# LoRa_GPS_Track_v1_2.net
KiCad netlist of a schematic drawn in EAGLE
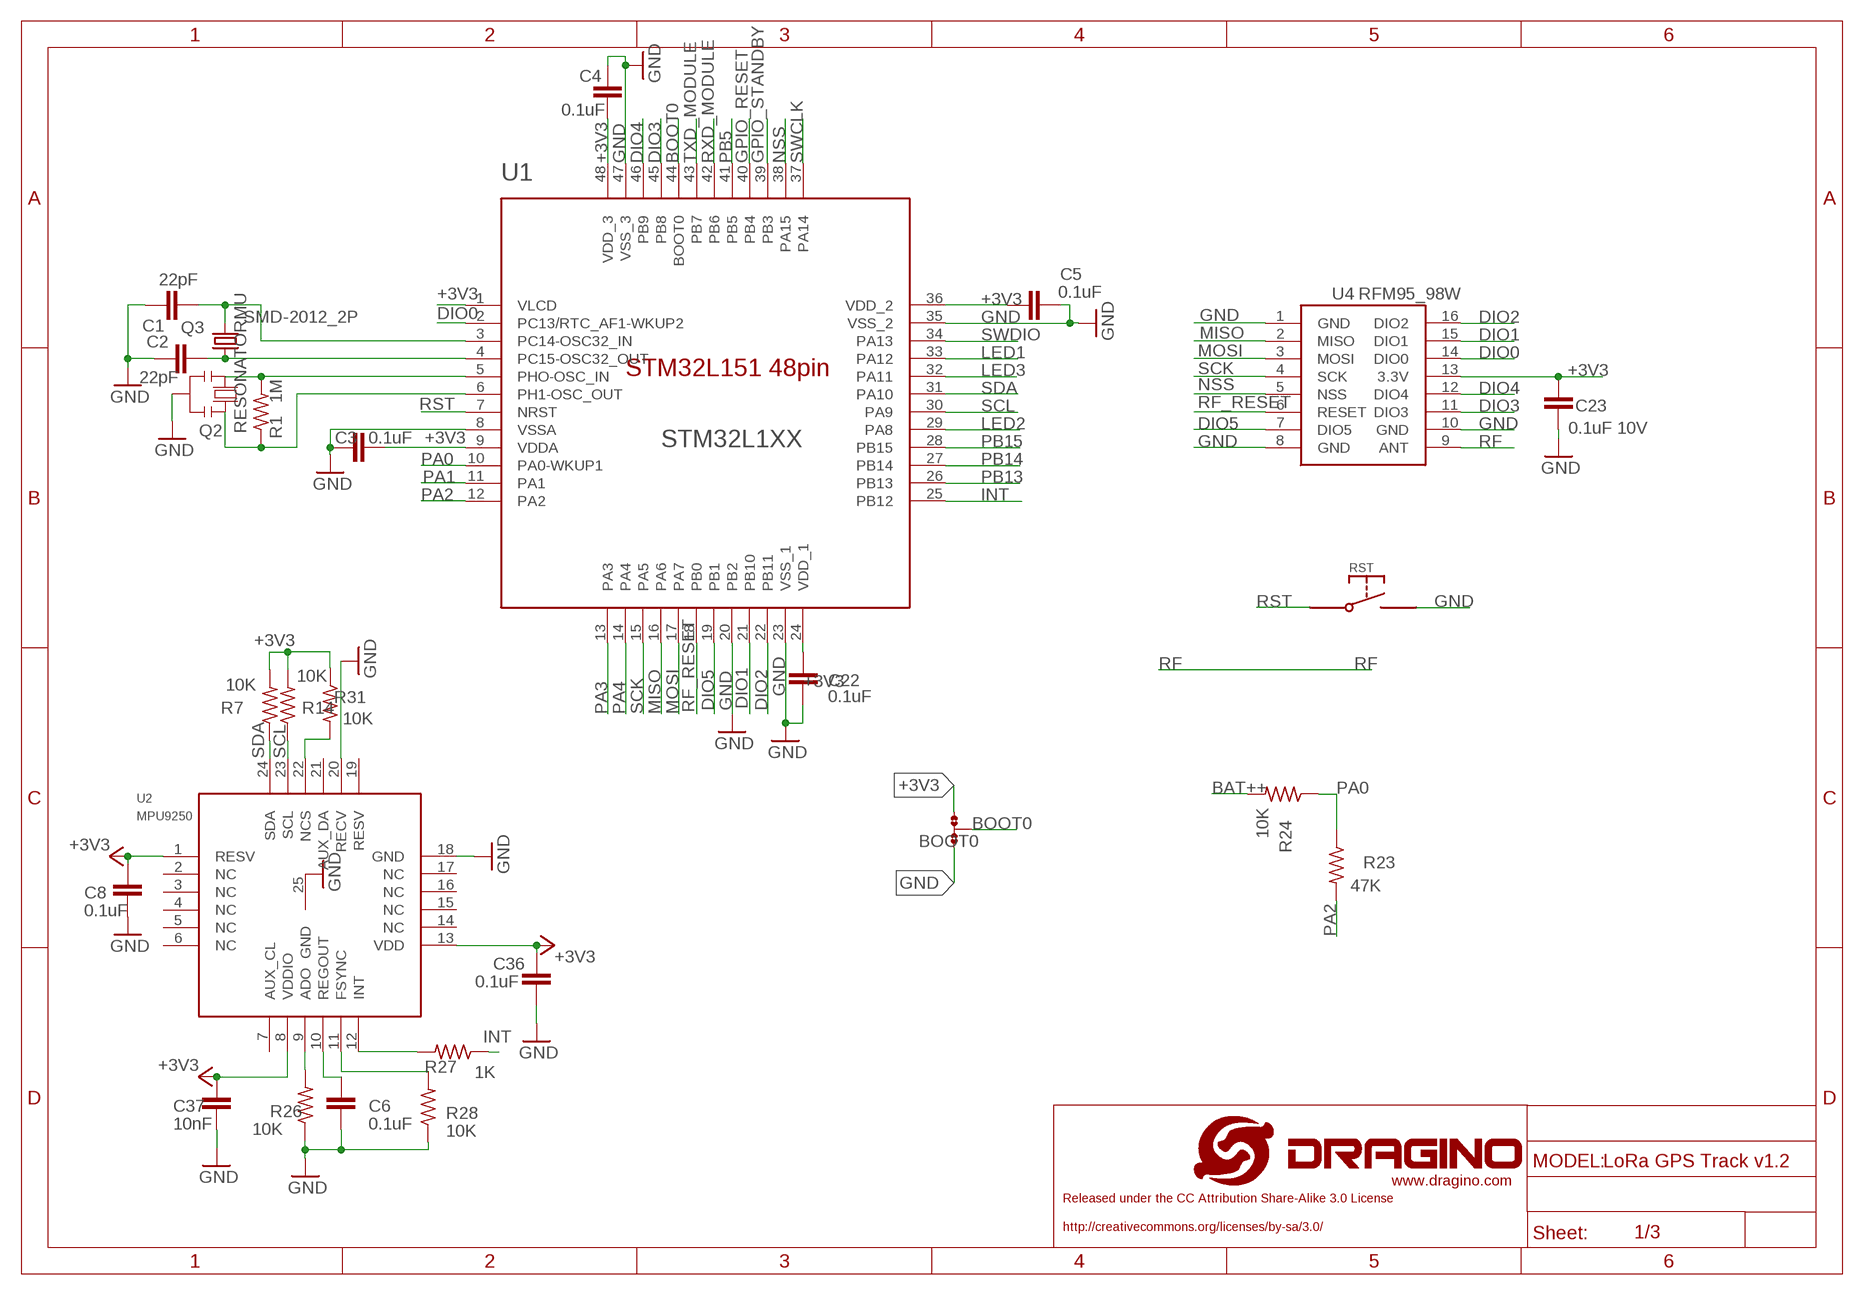
[diagram p0: schematic, sheet 1]
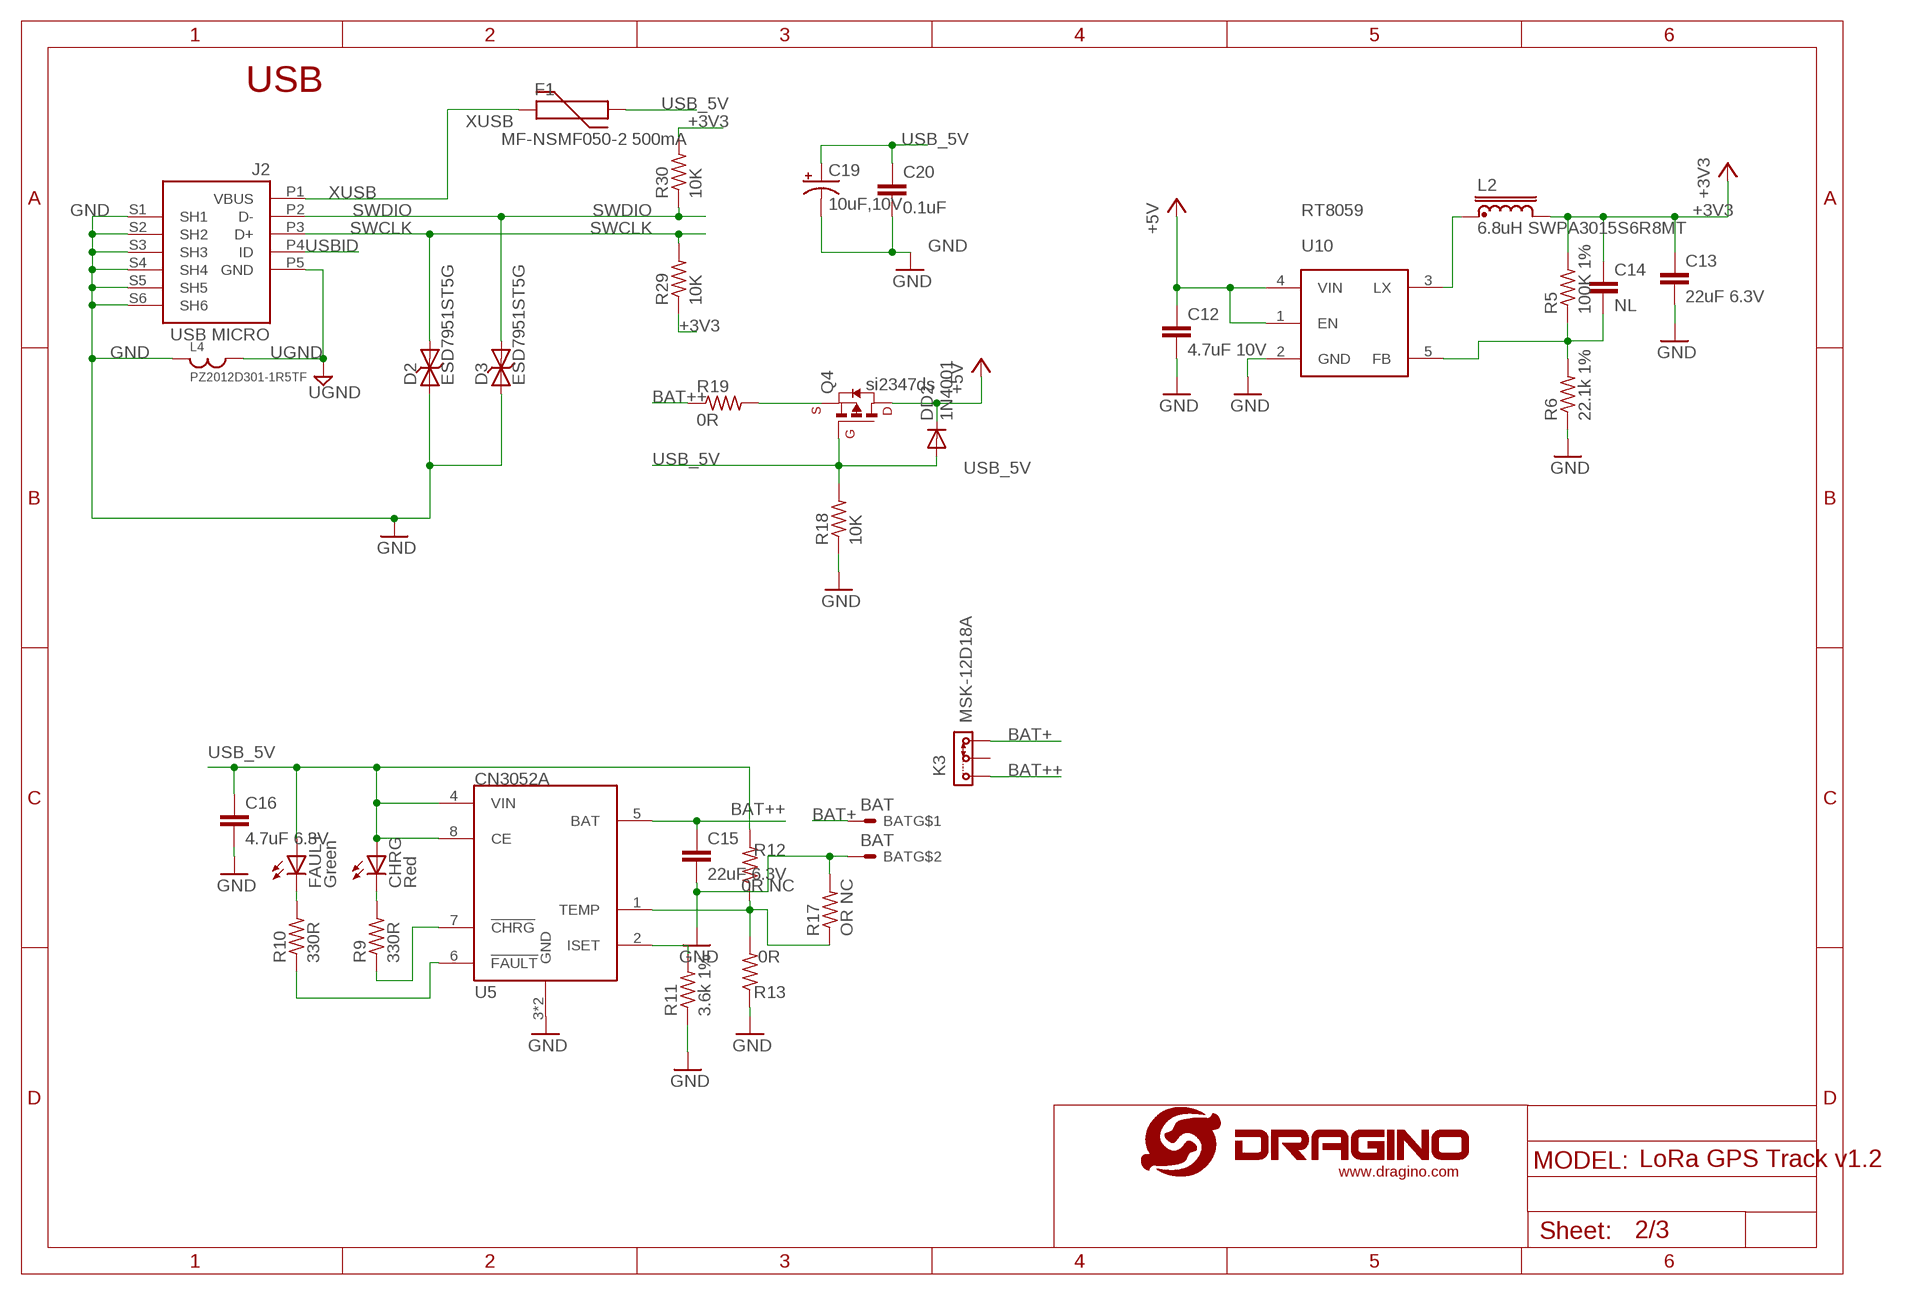
[diagram p1: schematic, sheet 2]
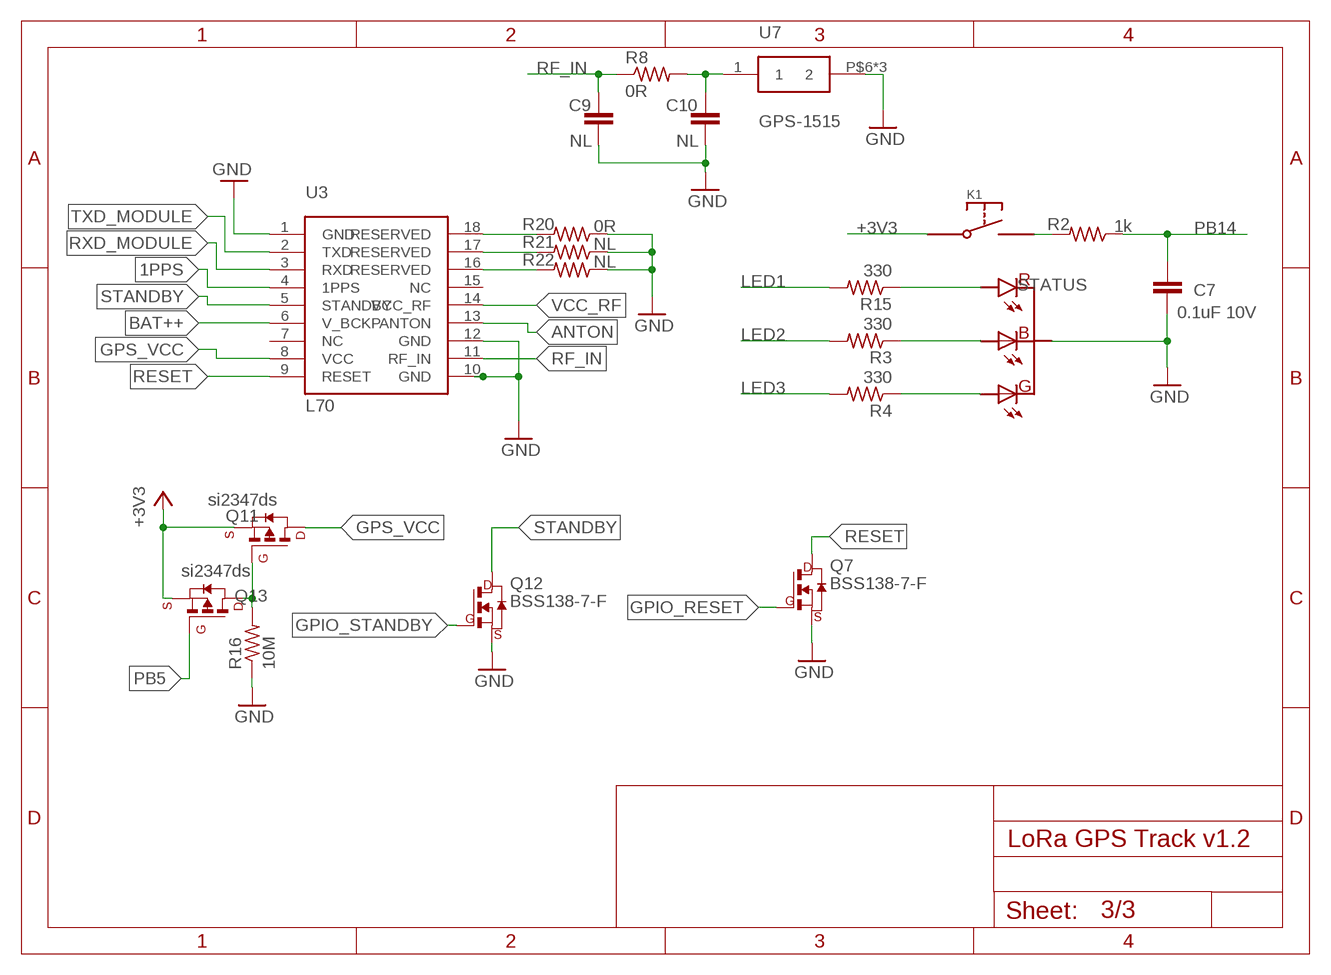
[diagram p2: schematic, sheet 3]

(export (version "E")
  (design (tool "Eeschema 10.0.6"))
  (components
    (comp (ref "C7")
      (value "0.1uF 10V")
      (footprint "eagle-import:C0402")
      (libsource (lib "eagle-import") (part "dragino-passive_C-EUC0402"))
    )
    (comp (ref "C9")
      (value "NL")
      (footprint "eagle-import:C0402")
      (libsource (lib "eagle-import") (part "dragino-passive_C-EUC0402"))
    )
    (comp (ref "C10")
      (value "NL")
      (footprint "eagle-import:C0402")
      (libsource (lib "eagle-import") (part "dragino-passive_C-EUC0402"))
    )
    (comp (ref "K1")
      (value "S-LAY")
      (footprint "eagle-import:KEY")
      (libsource (lib "eagle-import") (part "S-LAY"))
    )
    (comp (ref "Q7")
      (value "BSS138-7-F")
      (footprint "eagle-import:SOT-23")
      (libsource (lib "eagle-import") (part "NMOSFET"))
    )
    (comp (ref "Q11")
      (value "si2347ds")
      (footprint "eagle-import:SOT-23-HIGH-POWER")
      (libsource (lib "eagle-import") (part "P-MOSFET_HP"))
    )
    (comp (ref "Q12")
      (value "BSS138-7-F")
      (footprint "eagle-import:SOT-23")
      (libsource (lib "eagle-import") (part "NMOSFET"))
    )
    (comp (ref "Q13")
      (value "si2347ds")
      (footprint "eagle-import:SOT-23-HIGH-POWER")
      (libsource (lib "eagle-import") (part "P-MOSFET_HP"))
    )
    (comp (ref "R2")
      (value "1k")
      (footprint "eagle-import:R0402")
      (libsource (lib "eagle-import") (part "R-US_R0402"))
    )
    (comp (ref "R3")
      (value "330")
      (footprint "eagle-import:R0402")
      (libsource (lib "eagle-import") (part "R-US_R0402"))
    )
    (comp (ref "R4")
      (value "330")
      (footprint "eagle-import:R0402")
      (libsource (lib "eagle-import") (part "R-US_R0402"))
    )
    (comp (ref "R8")
      (value "0R")
      (footprint "eagle-import:R0402")
      (libsource (lib "eagle-import") (part "R-US_R0402"))
    )
    (comp (ref "R15")
      (value "330")
      (footprint "eagle-import:R0402")
      (libsource (lib "eagle-import") (part "R-US_R0402"))
    )
    (comp (ref "R16")
      (value "10M")
      (footprint "eagle-import:R0402")
      (libsource (lib "eagle-import") (part "R-US_R0402"))
    )
    (comp (ref "R20")
      (value "0R")
      (footprint "eagle-import:R0402")
      (libsource (lib "eagle-import") (part "R-US_R0402"))
    )
    (comp (ref "R21")
      (value "NL")
      (footprint "eagle-import:R0402")
      (libsource (lib "eagle-import") (part "R-US_R0402"))
    )
    (comp (ref "R22")
      (value "NL")
      (footprint "eagle-import:R0402")
      (libsource (lib "eagle-import") (part "R-US_R0402"))
    )
    (comp (ref "STATUS")
      (value "LED-RGB-THR-5MM-GNDSMD-3528")
      (footprint "eagle-import:LED-3528")
      (libsource (lib "eagle-import") (part "LED-RGB-THR-5MM-GNDSMD-3528"))
    )
    (comp (ref "U3")
      (value "L70")
      (footprint "eagle-import:L70")
      (libsource (lib "eagle-import") (part "L70"))
    )
    (comp (ref "U7")
      (value "GPS-1515")
      (footprint "eagle-import:GPS-15_15")
      (libsource (lib "eagle-import") (part "GPS-1515"))
    )
    (comp (ref "BAT")
      (value "BAT")
      (footprint "eagle-import:BAT")
      (libsource (lib "eagle-import") (part "BAT"))
    )
    (comp (ref "C12")
      (value "4.7uF 10V")
      (footprint "eagle-import:C0402")
      (libsource (lib "eagle-import") (part "C-EUC0402"))
    )
    (comp (ref "C13")
      (value "22uF 6.3V")
      (footprint "eagle-import:C0603")
      (libsource (lib "eagle-import") (part "C-EUC0603"))
    )
    (comp (ref "C14")
      (value "NL")
      (footprint "eagle-import:C0402")
      (libsource (lib "eagle-import") (part "C-EUC0402"))
    )
    (comp (ref "C15")
      (value "22uF 6.3V")
      (footprint "eagle-import:C0603")
      (libsource (lib "eagle-import") (part "C-EUC0603"))
    )
    (comp (ref "C16")
      (value "4.7uF 6.3V")
      (footprint "eagle-import:C0603")
      (libsource (lib "eagle-import") (part "C-EUC0603"))
    )
    (comp (ref "C19")
      (value "10uF,10V")
      (footprint "eagle-import:SMC_A")
      (libsource (lib "eagle-import") (part "CPOL-USSMCA"))
    )
    (comp (ref "C20")
      (value "0.1uF")
      (footprint "eagle-import:C0402")
      (libsource (lib "eagle-import") (part "dragino-passive_C-EUC0402"))
    )
    (comp (ref "CHRG")
      (value "Red")
      (footprint "eagle-import:DRAGINO_CHIPLED_0603")
      (libsource (lib "eagle-import") (part "DRAGINO_LEDCHIPLED_0603"))
    )
    (comp (ref "D2")
      (value "ESD7951ST5G")
      (footprint "eagle-import:SOD_923")
      (libsource (lib "eagle-import") (part "TVSSOD?923"))
    )
    (comp (ref "D3")
      (value "ESD7951ST5G")
      (footprint "eagle-import:SOD_923")
      (libsource (lib "eagle-import") (part "TVSSOD?923"))
    )
    (comp (ref "DD2")
      (value "1N4001")
      (footprint "eagle-import:DIODE_DO214AC")
      (libsource (lib "eagle-import") (part "DIODEDO214AC"))
    )
    (comp (ref "F1")
      (value "MF-NSMF050-2 500mA")
      (footprint "eagle-import:R1206$1")
      (libsource (lib "eagle-import") (part "FUSE1206"))
    )
    (comp (ref "FAULT")
      (value "Green")
      (footprint "eagle-import:DRAGINO_CHIPLED_0603")
      (libsource (lib "eagle-import") (part "DRAGINO_LEDCHIPLED_0603"))
    )
    (comp (ref "J2")
      (value "USB MICRO")
      (footprint "eagle-import:CON2_USB_MICRO_B_AT")
      (libsource (lib "eagle-import") (part "MYCON2_USB-MINI-B"))
    )
    (comp (ref "K3")
      (value "MSK-12D18A")
      (footprint "eagle-import:MSK-12D18A")
      (libsource (lib "eagle-import") (part "MSK-12D18A"))
    )
    (comp (ref "L2")
      (value "6.8uH SWPA3015S6R8MT")
      (footprint "eagle-import:SWPA3010S")
      (libsource (lib "eagle-import") (part "INDUCTORSWPA3010S"))
    )
    (comp (ref "L4")
      (value "PZ2012D301-1R5TF")
      (footprint "eagle-import:C0805$1")
      (libsource (lib "eagle-import") (part "BEADS0805"))
    )
    (comp (ref "Q4")
      (value "si2347ds")
      (footprint "eagle-import:SOT-23-HIGH-POWER")
      (libsource (lib "eagle-import") (part "P-MOSFET_HP"))
    )
    (comp (ref "R5")
      (value "100K 1%")
      (footprint "eagle-import:R0402")
      (libsource (lib "eagle-import") (part "R-US_R0402"))
    )
    (comp (ref "R6")
      (value "22.1k 1%")
      (footprint "eagle-import:R0402")
      (libsource (lib "eagle-import") (part "R-US_R0402"))
    )
    (comp (ref "R9")
      (value "330R")
      (footprint "eagle-import:R0402")
      (libsource (lib "eagle-import") (part "R-US_R0402"))
    )
    (comp (ref "R10")
      (value "330R")
      (footprint "eagle-import:R0402")
      (libsource (lib "eagle-import") (part "R-US_R0402"))
    )
    (comp (ref "R11")
      (value "3.6k 1%")
      (footprint "eagle-import:R0402")
      (libsource (lib "eagle-import") (part "R-US_R0402"))
    )
    (comp (ref "R12")
      (value "0R NC")
      (footprint "eagle-import:R0402")
      (libsource (lib "eagle-import") (part "R-US_R0402"))
    )
    (comp (ref "R13")
      (value "0R")
      (footprint "eagle-import:R0402")
      (libsource (lib "eagle-import") (part "R-US_R0402"))
    )
    (comp (ref "R17")
      (value "OR NC")
      (footprint "eagle-import:R0402")
      (libsource (lib "eagle-import") (part "R-US_R0402"))
    )
    (comp (ref "R18")
      (value "10K")
      (footprint "eagle-import:R0402")
      (libsource (lib "eagle-import") (part "R-US_R0402"))
    )
    (comp (ref "R19")
      (value "0R")
      (footprint "eagle-import:R0805")
      (libsource (lib "eagle-import") (part "R-US_R0805"))
    )
    (comp (ref "R29")
      (value "10K")
      (footprint "eagle-import:R0402")
      (libsource (lib "eagle-import") (part "R-US_R0402"))
    )
    (comp (ref "R30")
      (value "10K")
      (footprint "eagle-import:R0402")
      (libsource (lib "eagle-import") (part "R-US_R0402"))
    )
    (comp (ref "U5")
      (value "CN3052A")
      (footprint "eagle-import:CN3052A")
      (libsource (lib "eagle-import") (part "CN3052A"))
    )
    (comp (ref "U10")
      (value "RT8059")
      (footprint "eagle-import:SOT23-5")
      (libsource (lib "eagle-import") (part "RT8059"))
    )
    (comp (ref "BOOT0")
      (value "0R-JUMPA0R-JMP-0402")
      (footprint "eagle-import:A0R-JMP-0402")
      (libsource (lib "eagle-import") (part "0R-JUMPA0R-JMP-0402"))
    )
    (comp (ref "C1")
      (value "22pF")
      (footprint "eagle-import:C0402")
      (libsource (lib "eagle-import") (part "dragino-passive_C-EUC0402"))
    )
    (comp (ref "C2")
      (value "22pF")
      (footprint "eagle-import:C0402")
      (libsource (lib "eagle-import") (part "dragino-passive_C-EUC0402"))
    )
    (comp (ref "C3")
      (value "0.1uF")
      (footprint "eagle-import:C0402")
      (libsource (lib "eagle-import") (part "dragino-passive_C-EUC0402"))
    )
    (comp (ref "C4")
      (value "0.1uF")
      (footprint "eagle-import:C0402")
      (libsource (lib "eagle-import") (part "dragino-passive_C-EUC0402"))
    )
    (comp (ref "C5")
      (value "0.1uF")
      (footprint "eagle-import:C0402")
      (libsource (lib "eagle-import") (part "dragino-passive_C-EUC0402"))
    )
    (comp (ref "C6")
      (value "0.1uF")
      (footprint "eagle-import:C0402")
      (libsource (lib "eagle-import") (part "C-EUC0402"))
    )
    (comp (ref "C8")
      (value "0.1uF")
      (footprint "eagle-import:C0402")
      (libsource (lib "eagle-import") (part "C-EUC0402"))
    )
    (comp (ref "C22")
      (value "0.1uF")
      (footprint "eagle-import:C0402")
      (libsource (lib "eagle-import") (part "dragino-passive_C-EUC0402"))
    )
    (comp (ref "C23")
      (value "0.1uF 10V")
      (footprint "eagle-import:C0402")
      (libsource (lib "eagle-import") (part "dragino-passive_C-EUC0402"))
    )
    (comp (ref "C36")
      (value "0.1uF")
      (footprint "eagle-import:C0402")
      (libsource (lib "eagle-import") (part "C-EUC0402"))
    )
    (comp (ref "C37")
      (value "10nF")
      (footprint "eagle-import:C0402")
      (libsource (lib "eagle-import") (part "C-EUC0402"))
    )
    (comp (ref "Q2")
      (value "RESONATORMU")
      (footprint "eagle-import:RESONATOR")
      (libsource (lib "eagle-import") (part "RESONATORMU"))
    )
    (comp (ref "Q3")
      (value "SMD-2012_2P")
      (footprint "eagle-import:32.768K")
      (libsource (lib "eagle-import") (part "SMD-2012_2P"))
    )
    (comp (ref "R1")
      (value "1M")
      (footprint "eagle-import:R0402")
      (libsource (lib "eagle-import") (part "R-US_R0402"))
    )
    (comp (ref "R7")
      (value "10K")
      (footprint "eagle-import:R0402")
      (libsource (lib "eagle-import") (part "R-US_R0402"))
    )
    (comp (ref "R14")
      (value "10K")
      (footprint "eagle-import:R0402")
      (libsource (lib "eagle-import") (part "R-US_R0402"))
    )
    (comp (ref "R23")
      (value "47K")
      (footprint "eagle-import:R0402")
      (libsource (lib "eagle-import") (part "R-US_R0402"))
    )
    (comp (ref "R24")
      (value "10K")
      (footprint "eagle-import:R0402")
      (libsource (lib "eagle-import") (part "R-US_R0402"))
    )
    (comp (ref "R26")
      (value "10K")
      (footprint "eagle-import:R0402")
      (libsource (lib "eagle-import") (part "R-US_R0402"))
    )
    (comp (ref "R27")
      (value "1K")
      (footprint "eagle-import:R0402")
      (libsource (lib "eagle-import") (part "R-US_R0402"))
    )
    (comp (ref "R28")
      (value "10K")
      (footprint "eagle-import:R0402")
      (libsource (lib "eagle-import") (part "R-US_R0402"))
    )
    (comp (ref "R31")
      (value "10K")
      (footprint "eagle-import:R0402")
      (libsource (lib "eagle-import") (part "R-US_R0402"))
    )
    (comp (ref "RST")
      (value "SWITCHTS-017")
      (footprint "eagle-import:TS-017")
      (libsource (lib "eagle-import") (part "SWITCHTS-017"))
    )
    (comp (ref "U1")
      (value "STM32L1XX")
      (footprint "eagle-import:STM32L1XX")
      (libsource (lib "eagle-import") (part "STM32L1XX"))
    )
    (comp (ref "U2")
      (value "MPU9250")
      (footprint "eagle-import:QFN-24")
      (libsource (lib "eagle-import") (part "MPU9250"))
    )
    (comp (ref "U4")
      (value "RFM95_98W")
      (footprint "eagle-import:RFM95_98W")
      (libsource (lib "eagle-import") (part "RFM95_98W"))
    )
  )
  (nets
    (net (code "1") (name "+3V3") (class "Default")
      (node (ref "BOOT0") (pin "1") (pinfunction "1_1") (pintype "passive"))
      (node (ref "C13") (pin "1") (pinfunction "1_1") (pintype "passive"))
      (node (ref "C14") (pin "1") (pinfunction "1_1") (pintype "passive"))
      (node (ref "C22") (pin "2") (pinfunction "2_2") (pintype "passive"))
      (node (ref "C23") (pin "2") (pinfunction "2_2") (pintype "passive"))
      (node (ref "C3") (pin "1") (pinfunction "1_1") (pintype "passive"))
      (node (ref "C36") (pin "2") (pinfunction "2_2") (pintype "passive"))
      (node (ref "C37") (pin "2") (pinfunction "2_2") (pintype "passive"))
      (node (ref "C4") (pin "1") (pinfunction "1_1") (pintype "passive"))
      (node (ref "C5") (pin "2") (pinfunction "2_2") (pintype "passive"))
      (node (ref "C8") (pin "2") (pinfunction "2_2") (pintype "passive"))
      (node (ref "K1") (pin "1") (pinfunction "P$1_1") (pintype "bidirectional"))
      (node (ref "K1") (pin "2") (pinfunction "P$1_2") (pintype "bidirectional"))
      (node (ref "K1") (pin "5") (pinfunction "P$1_5") (pintype "bidirectional"))
      (node (ref "L2") (pin "P$2") (pinfunction "4_P$2") (pintype "passive"))
      (node (ref "Q11") (pin "2") (pinfunction "S_2") (pintype "passive"))
      (node (ref "Q13") (pin "2") (pinfunction "S_2") (pintype "passive"))
      (node (ref "R14") (pin "2") (pinfunction "2_2") (pintype "passive"))
      (node (ref "R29") (pin "1") (pinfunction "1_1") (pintype "passive"))
      (node (ref "R30") (pin "2") (pinfunction "2_2") (pintype "passive"))
      (node (ref "R31") (pin "1") (pinfunction "1_1") (pintype "passive"))
      (node (ref "R5") (pin "2") (pinfunction "2_2") (pintype "passive"))
      (node (ref "R7") (pin "2") (pinfunction "2_2") (pintype "passive"))
      (node (ref "U1") (pin "1") (pinfunction "VLCD_1") (pintype "bidirectional"))
      (node (ref "U1") (pin "24") (pinfunction "VDD_1_24") (pintype "bidirectional"))
      (node (ref "U1") (pin "36") (pinfunction "VDD_2_36") (pintype "bidirectional"))
      (node (ref "U1") (pin "48") (pinfunction "VDD_3_48") (pintype "bidirectional"))
      (node (ref "U1") (pin "9") (pinfunction "VDDA_9") (pintype "bidirectional"))
      (node (ref "U2") (pin "1") (pinfunction "RESV_1") (pintype "bidirectional"))
      (node (ref "U2") (pin "13") (pinfunction "VDD_13") (pintype "bidirectional"))
      (node (ref "U2") (pin "8") (pinfunction "VDDIO_8") (pintype "bidirectional"))
      (node (ref "U4") (pin "13") (pinfunction "3.3V_13") (pintype "power_in"))
    )
    (net (code "2") (name "+5V") (class "Default")
      (node (ref "C12") (pin "1") (pinfunction "1_1") (pintype "passive"))
      (node (ref "DD2") (pin "C") (pinfunction "C_C") (pintype "passive"))
      (node (ref "Q4") (pin "1") (pinfunction "D_1") (pintype "passive"))
      (node (ref "U10") (pin "1") (pinfunction "EN_1") (pintype "bidirectional"))
      (node (ref "U10") (pin "4") (pinfunction "VIN_4") (pintype "bidirectional"))
    )
    (net (code "3") (name "1PPS") (class "Default")
      (node (ref "U3") (pin "4") (pinfunction "1PPS_4") (pintype "bidirectional"))
    )
    (net (code "4") (name "ANTON") (class "Default")
      (node (ref "U3") (pin "13") (pinfunction "ANTON_13") (pintype "bidirectional"))
    )
    (net (code "5") (name "BAT+") (class "Default")
      (node (ref "BAT") (pin "P$1") (pinfunction "S_P$1") (pintype "passive"))
      (node (ref "K3") (pin "3") (pinfunction "3_3") (pintype "passive"))
    )
    (net (code "6") (name "BAT++") (class "Default")
      (node (ref "C15") (pin "1") (pinfunction "1_1") (pintype "passive"))
      (node (ref "K3") (pin "1") (pinfunction "1_1") (pintype "passive"))
      (node (ref "R19") (pin "1") (pinfunction "1_1") (pintype "passive"))
      (node (ref "R24") (pin "2") (pinfunction "2_2") (pintype "passive"))
      (node (ref "U3") (pin "6") (pinfunction "V_BCKP_6") (pintype "bidirectional"))
      (node (ref "U5") (pin "5") (pinfunction "BAT_5") (pintype "bidirectional"))
    )
    (net (code "7") (name "BOOT0") (class "Default")
      (node (ref "BOOT0") (pin "2") (pinfunction "2_2") (pintype "passive"))
      (node (ref "U1") (pin "44") (pinfunction "BOOT0_44") (pintype "bidirectional"))
    )
    (net (code "8") (name "DIO0") (class "Default")
      (node (ref "U1") (pin "2") (pinfunction "PC13/RTC_AF1-WKUP2_2") (pintype "bidirectional"))
      (node (ref "U4") (pin "14") (pinfunction "DIO0_14") (pintype "bidirectional"))
    )
    (net (code "9") (name "DIO1") (class "Default")
      (node (ref "U1") (pin "21") (pinfunction "PB10_21") (pintype "bidirectional"))
      (node (ref "U4") (pin "15") (pinfunction "DIO1_15") (pintype "bidirectional"))
    )
    (net (code "10") (name "DIO2") (class "Default")
      (node (ref "U1") (pin "22") (pinfunction "PB11_22") (pintype "bidirectional"))
      (node (ref "U4") (pin "16") (pinfunction "DIO2_16") (pintype "bidirectional"))
    )
    (net (code "11") (name "DIO3") (class "Default")
      (node (ref "U1") (pin "45") (pinfunction "PB8_45") (pintype "bidirectional"))
      (node (ref "U4") (pin "11") (pinfunction "DIO3_11") (pintype "bidirectional"))
    )
    (net (code "12") (name "DIO4") (class "Default")
      (node (ref "U1") (pin "46") (pinfunction "PB9_46") (pintype "bidirectional"))
      (node (ref "U4") (pin "12") (pinfunction "DIO4_12") (pintype "bidirectional"))
    )
    (net (code "13") (name "DIO5") (class "Default")
      (node (ref "U1") (pin "19") (pinfunction "PB1_19") (pintype "bidirectional"))
      (node (ref "U4") (pin "7") (pinfunction "DIO5_7") (pintype "bidirectional"))
    )
    (net (code "14") (name "GND") (class "Default")
      (node (ref "BAT") (pin "P$2") (pinfunction "S_P$2") (pintype "passive"))
      (node (ref "BOOT0") (pin "3") (pinfunction "3_3") (pintype "passive"))
      (node (ref "C1") (pin "1") (pinfunction "1_1") (pintype "passive"))
      (node (ref "C10") (pin "2") (pinfunction "2_2") (pintype "passive"))
      (node (ref "C12") (pin "2") (pinfunction "2_2") (pintype "passive"))
      (node (ref "C13") (pin "2") (pinfunction "2_2") (pintype "passive"))
      (node (ref "C15") (pin "2") (pinfunction "2_2") (pintype "passive"))
      (node (ref "C16") (pin "2") (pinfunction "2_2") (pintype "passive"))
      (node (ref "C19") (pin "-") (pinfunction "-_-") (pintype "passive"))
      (node (ref "C2") (pin "1") (pinfunction "1_1") (pintype "passive"))
      (node (ref "C20") (pin "2") (pinfunction "2_2") (pintype "passive"))
      (node (ref "C22") (pin "1") (pinfunction "1_1") (pintype "passive"))
      (node (ref "C23") (pin "1") (pinfunction "1_1") (pintype "passive"))
      (node (ref "C3") (pin "2") (pinfunction "2_2") (pintype "passive"))
      (node (ref "C36") (pin "1") (pinfunction "1_1") (pintype "passive"))
      (node (ref "C37") (pin "1") (pinfunction "1_1") (pintype "passive"))
      (node (ref "C4") (pin "2") (pinfunction "2_2") (pintype "passive"))
      (node (ref "C5") (pin "1") (pinfunction "1_1") (pintype "passive"))
      (node (ref "C6") (pin "1") (pinfunction "1_1") (pintype "passive"))
      (node (ref "C7") (pin "1") (pinfunction "1_1") (pintype "passive"))
      (node (ref "C8") (pin "1") (pinfunction "1_1") (pintype "passive"))
      (node (ref "C9") (pin "2") (pinfunction "2_2") (pintype "passive"))
      (node (ref "D2") (pin "P$1") (pinfunction "1_P$1") (pintype "passive"))
      (node (ref "D3") (pin "P$1") (pinfunction "1_P$1") (pintype "passive"))
      (node (ref "J2") (pin "S1") (pinfunction "SH1_S1") (pintype "passive"))
      (node (ref "J2") (pin "S2") (pinfunction "SH2_S2") (pintype "passive"))
      (node (ref "J2") (pin "S3") (pinfunction "SH3_S3") (pintype "passive"))
      (node (ref "J2") (pin "S4") (pinfunction "SH4_S4") (pintype "passive"))
      (node (ref "J2") (pin "S5") (pinfunction "SH5_S5") (pintype "passive"))
      (node (ref "J2") (pin "S6") (pinfunction "SH6_S6") (pintype "passive"))
      (node (ref "L4") (pin "1") (pinfunction "P$1_1") (pintype "bidirectional"))
      (node (ref "Q12") (pin "2") (pinfunction "S_2") (pintype "passive"))
      (node (ref "Q2") (pin "2") (pinfunction "2_2") (pintype "passive"))
      (node (ref "Q7") (pin "2") (pinfunction "S_2") (pintype "passive"))
      (node (ref "R11") (pin "1") (pinfunction "1_1") (pintype "passive"))
      (node (ref "R13") (pin "1") (pinfunction "1_1") (pintype "passive"))
      (node (ref "R16") (pin "1") (pinfunction "1_1") (pintype "passive"))
      (node (ref "R17") (pin "2") (pinfunction "2_2") (pintype "passive"))
      (node (ref "R18") (pin "1") (pinfunction "1_1") (pintype "passive"))
      (node (ref "R20") (pin "1") (pinfunction "1_1") (pintype "passive"))
      (node (ref "R21") (pin "1") (pinfunction "1_1") (pintype "passive"))
      (node (ref "R22") (pin "1") (pinfunction "1_1") (pintype "passive"))
      (node (ref "R26") (pin "1") (pinfunction "1_1") (pintype "passive"))
      (node (ref "R28") (pin "1") (pinfunction "1_1") (pintype "passive"))
      (node (ref "R6") (pin "1") (pinfunction "1_1") (pintype "passive"))
      (node (ref "RST") (pin "P$2") (pinfunction "P$2_P$2") (pintype "bidirectional"))
      (node (ref "STATUS") (pin "+") (pinfunction "C_+") (pintype "passive"))
      (node (ref "U1") (pin "20") (pinfunction "PB2_20") (pintype "bidirectional"))
      (node (ref "U1") (pin "23") (pinfunction "VSS_1_23") (pintype "bidirectional"))
      (node (ref "U1") (pin "35") (pinfunction "VSS_2_35") (pintype "bidirectional"))
      (node (ref "U1") (pin "47") (pinfunction "VSS_3_47") (pintype "bidirectional"))
      (node (ref "U1") (pin "8") (pinfunction "VSSA_8") (pintype "bidirectional"))
      (node (ref "U10") (pin "2") (pinfunction "GND_2") (pintype "bidirectional"))
      (node (ref "U2") (pin "18") (pinfunction "GND_18") (pintype "bidirectional"))
      (node (ref "U2") (pin "20") (pinfunction "RECV_20") (pintype "bidirectional"))
      (node (ref "U2") (pin "25") (pinfunction "GND_25") (pintype "bidirectional"))
      (node (ref "U3") (pin "1") (pinfunction "GND_1") (pintype "bidirectional"))
      (node (ref "U3") (pin "10") (pinfunction "GND_10") (pintype "bidirectional"))
      (node (ref "U3") (pin "12") (pinfunction "GND_12") (pintype "bidirectional"))
      (node (ref "U4") (pin "1") (pinfunction "GND_1") (pintype "power_in"))
      (node (ref "U4") (pin "10") (pinfunction "GND_10") (pintype "power_in"))
      (node (ref "U4") (pin "8") (pinfunction "GND_8") (pintype "power_in"))
      (node (ref "U5") (pin "3") (pinfunction "GND_3") (pintype "bidirectional"))
      (node (ref "U5") (pin "P$1") (pinfunction "GND_P$1") (pintype "bidirectional"))
      (node (ref "U7") (pin "P$6") (pinfunction "2_P$6") (pintype "bidirectional"))
      (node (ref "U7") (pin "P$7") (pinfunction "2_P$7") (pintype "bidirectional"))
      (node (ref "U7") (pin "P$8") (pinfunction "2_P$8") (pintype "bidirectional"))
    )
    (net (code "15") (name "GPIO_RESET") (class "Default")
      (node (ref "Q7") (pin "3") (pinfunction "G_3") (pintype "passive"))
      (node (ref "U1") (pin "40") (pinfunction "PB4_40") (pintype "bidirectional"))
    )
    (net (code "16") (name "GPIO_STANDBY") (class "Default")
      (node (ref "Q12") (pin "3") (pinfunction "G_3") (pintype "passive"))
      (node (ref "U1") (pin "39") (pinfunction "PB3_39") (pintype "bidirectional"))
    )
    (net (code "17") (name "GPS_VCC") (class "Default")
      (node (ref "Q11") (pin "1") (pinfunction "D_1") (pintype "passive"))
      (node (ref "U3") (pin "8") (pinfunction "VCC_8") (pintype "bidirectional"))
    )
    (net (code "18") (name "INT") (class "Default")
      (node (ref "R27") (pin "1") (pinfunction "1_1") (pintype "passive"))
      (node (ref "U1") (pin "25") (pinfunction "PB12_25") (pintype "bidirectional"))
    )
    (net (code "19") (name "LED1") (class "Default")
      (node (ref "R15") (pin "2") (pinfunction "2_2") (pintype "passive"))
      (node (ref "U1") (pin "33") (pinfunction "PA12_33") (pintype "bidirectional"))
    )
    (net (code "20") (name "LED2") (class "Default")
      (node (ref "R3") (pin "2") (pinfunction "2_2") (pintype "passive"))
      (node (ref "U1") (pin "29") (pinfunction "PA8_29") (pintype "bidirectional"))
    )
    (net (code "21") (name "LED3") (class "Default")
      (node (ref "R4") (pin "2") (pinfunction "2_2") (pintype "passive"))
      (node (ref "U1") (pin "32") (pinfunction "PA11_32") (pintype "bidirectional"))
    )
    (net (code "22") (name "MISO") (class "Default")
      (node (ref "U1") (pin "16") (pinfunction "PA6_16") (pintype "bidirectional"))
      (node (ref "U4") (pin "2") (pinfunction "MISO_2") (pintype "bidirectional"))
    )
    (net (code "23") (name "MOSI") (class "Default")
      (node (ref "U1") (pin "17") (pinfunction "PA7_17") (pintype "bidirectional"))
      (node (ref "U4") (pin "3") (pinfunction "MOSI_3") (pintype "bidirectional"))
    )
    (net (code "24") (name "NSS") (class "Default")
      (node (ref "U1") (pin "38") (pinfunction "PA15_38") (pintype "bidirectional"))
      (node (ref "U4") (pin "5") (pinfunction "NSS_5") (pintype "bidirectional"))
    )
    (net (code "25") (name "Net-(C10-Pad1)") (class "Default")
      (node (ref "C10") (pin "1") (pinfunction "1_1") (pintype "passive"))
      (node (ref "R8") (pin "2") (pinfunction "2_2") (pintype "passive"))
      (node (ref "U7") (pin "1") (pinfunction "1_1") (pintype "bidirectional"))
    )
    (net (code "26") (name "Net-(CHRG-PadC)") (class "Default")
      (node (ref "CHRG") (pin "C") (pinfunction "C_C") (pintype "passive"))
      (node (ref "R9") (pin "2") (pinfunction "2_2") (pintype "passive"))
    )
    (net (code "27") (name "Net-(FAULT-PadC)") (class "Default")
      (node (ref "FAULT") (pin "C") (pinfunction "C_C") (pintype "passive"))
      (node (ref "R10") (pin "2") (pinfunction "2_2") (pintype "passive"))
    )
    (net (code "28") (name "Net-(K1-P$2-Pad3)") (class "Default")
      (node (ref "K1") (pin "3") (pinfunction "P$2_3") (pintype "bidirectional"))
      (node (ref "K1") (pin "4") (pinfunction "P$2_4") (pintype "bidirectional"))
      (node (ref "K1") (pin "6") (pinfunction "P$2_6") (pintype "bidirectional"))
      (node (ref "R2") (pin "2") (pinfunction "2_2") (pintype "passive"))
    )
    (net (code "29") (name "Net-(L2-1)") (class "Default")
      (node (ref "L2") (pin "P$1") (pinfunction "1_P$1") (pintype "passive"))
      (node (ref "U10") (pin "3") (pinfunction "LX_3") (pintype "bidirectional"))
    )
    (net (code "30") (name "Net-(Q3-1)") (class "Default")
      (node (ref "C2") (pin "2") (pinfunction "2_2") (pintype "passive"))
      (node (ref "Q3") (pin "3") (pinfunction "1_3") (pintype "passive"))
      (node (ref "U1") (pin "4") (pinfunction "PC15-OSC32_OUT_4") (pintype "bidirectional"))
    )
    (net (code "31") (name "Net-(Q3-2)") (class "Default")
      (node (ref "C1") (pin "2") (pinfunction "2_2") (pintype "passive"))
      (node (ref "Q3") (pin "4") (pinfunction "2_4") (pintype "passive"))
      (node (ref "U1") (pin "3") (pinfunction "PC14-OSC32_IN_3") (pintype "bidirectional"))
    )
    (net (code "32") (name "Net-(Q4-S)") (class "Default")
      (node (ref "Q4") (pin "2") (pinfunction "S_2") (pintype "passive"))
      (node (ref "R19") (pin "2") (pinfunction "2_2") (pintype "passive"))
    )
    (net (code "33") (name "Net-(Q11-G)") (class "Default")
      (node (ref "Q11") (pin "3") (pinfunction "G_3") (pintype "passive"))
      (node (ref "Q13") (pin "1") (pinfunction "D_1") (pintype "passive"))
      (node (ref "R16") (pin "2") (pinfunction "2_2") (pintype "passive"))
    )
    (net (code "34") (name "Net-(R20-Pad2)") (class "Default")
      (node (ref "R20") (pin "2") (pinfunction "2_2") (pintype "passive"))
      (node (ref "U3") (pin "18") (pinfunction "RESERVED_18") (pintype "bidirectional"))
    )
    (net (code "35") (name "Net-(R21-Pad2)") (class "Default")
      (node (ref "R21") (pin "2") (pinfunction "2_2") (pintype "passive"))
      (node (ref "U3") (pin "17") (pinfunction "RESERVED_17") (pintype "bidirectional"))
    )
    (net (code "36") (name "Net-(R22-Pad2)") (class "Default")
      (node (ref "R22") (pin "2") (pinfunction "2_2") (pintype "passive"))
      (node (ref "U3") (pin "16") (pinfunction "RESERVED_16") (pintype "bidirectional"))
    )
    (net (code "37") (name "Net-(STATUS-1)") (class "Default")
      (node (ref "R15") (pin "1") (pinfunction "1_1") (pintype "passive"))
      (node (ref "STATUS") (pin "R-") (pinfunction "1_R-") (pintype "passive"))
    )
    (net (code "38") (name "Net-(STATUS-3)") (class "Default")
      (node (ref "R3") (pin "1") (pinfunction "1_1") (pintype "passive"))
      (node (ref "STATUS") (pin "B-") (pinfunction "3_B-") (pintype "passive"))
    )
    (net (code "39") (name "Net-(STATUS-4)") (class "Default")
      (node (ref "R4") (pin "1") (pinfunction "1_1") (pintype "passive"))
      (node (ref "STATUS") (pin "G-") (pinfunction "4_G-") (pintype "passive"))
    )
    (net (code "40") (name "Net-(U1-PH1-OSC_OUT)") (class "Default")
      (node (ref "Q2") (pin "3") (pinfunction "3_3") (pintype "passive"))
      (node (ref "R1") (pin "1") (pinfunction "1_1") (pintype "passive"))
      (node (ref "U1") (pin "6") (pinfunction "PH1-OSC_OUT_6") (pintype "bidirectional"))
    )
    (net (code "41") (name "Net-(U1-PHO-OSC_IN)") (class "Default")
      (node (ref "Q2") (pin "1") (pinfunction "1_1") (pintype "passive"))
      (node (ref "R1") (pin "2") (pinfunction "2_2") (pintype "passive"))
      (node (ref "U1") (pin "5") (pinfunction "PHO-OSC_IN_5") (pintype "bidirectional"))
    )
    (net (code "42") (name "Net-(U2-ADO)") (class "Default")
      (node (ref "R26") (pin "2") (pinfunction "2_2") (pintype "passive"))
      (node (ref "U2") (pin "9") (pinfunction "ADO_9") (pintype "bidirectional"))
    )
    (net (code "43") (name "Net-(U2-FSYNC)") (class "Default")
      (node (ref "R28") (pin "2") (pinfunction "2_2") (pintype "passive"))
      (node (ref "U2") (pin "11") (pinfunction "FSYNC_11") (pintype "bidirectional"))
    )
    (net (code "44") (name "Net-(U2-INT)") (class "Default")
      (node (ref "R27") (pin "2") (pinfunction "2_2") (pintype "passive"))
      (node (ref "U2") (pin "12") (pinfunction "INT_12") (pintype "bidirectional"))
    )
    (net (code "45") (name "Net-(U2-NCS)") (class "Default")
      (node (ref "R31") (pin "2") (pinfunction "2_2") (pintype "passive"))
      (node (ref "U2") (pin "22") (pinfunction "NCS_22") (pintype "bidirectional"))
    )
    (net (code "46") (name "Net-(U2-REGOUT)") (class "Default")
      (node (ref "C6") (pin "2") (pinfunction "2_2") (pintype "passive"))
      (node (ref "U2") (pin "10") (pinfunction "REGOUT_10") (pintype "bidirectional"))
    )
    (net (code "47") (name "Net-(U5-ISET)") (class "Default")
      (node (ref "R11") (pin "2") (pinfunction "2_2") (pintype "passive"))
      (node (ref "U5") (pin "2") (pinfunction "ISET_2") (pintype "bidirectional"))
    )
    (net (code "48") (name "Net-(U5-TEMP)") (class "Default")
      (node (ref "R12") (pin "1") (pinfunction "1_1") (pintype "passive"))
      (node (ref "R13") (pin "2") (pinfunction "2_2") (pintype "passive"))
      (node (ref "R17") (pin "1") (pinfunction "1_1") (pintype "passive"))
      (node (ref "U5") (pin "1") (pinfunction "TEMP_1") (pintype "bidirectional"))
    )
    (net (code "49") (name "Net-(U5-~{CHRG})") (class "Default")
      (node (ref "R9") (pin "1") (pinfunction "1_1") (pintype "passive"))
      (node (ref "U5") (pin "7") (pinfunction "~{CHRG}_7") (pintype "bidirectional"))
    )
    (net (code "50") (name "Net-(U5-~{FAULT})") (class "Default")
      (node (ref "R10") (pin "1") (pinfunction "1_1") (pintype "passive"))
      (node (ref "U5") (pin "6") (pinfunction "~{FAULT}_6") (pintype "bidirectional"))
    )
    (net (code "51") (name "Net-(U10-FB)") (class "Default")
      (node (ref "C14") (pin "2") (pinfunction "2_2") (pintype "passive"))
      (node (ref "R5") (pin "1") (pinfunction "1_1") (pintype "passive"))
      (node (ref "R6") (pin "2") (pinfunction "2_2") (pintype "passive"))
      (node (ref "U10") (pin "5") (pinfunction "FB_5") (pintype "bidirectional"))
    )
    (net (code "52") (name "PA0") (class "Default")
      (node (ref "R23") (pin "1") (pinfunction "1_1") (pintype "passive"))
      (node (ref "R24") (pin "1") (pinfunction "1_1") (pintype "passive"))
      (node (ref "U1") (pin "10") (pinfunction "PA0-WKUP1_10") (pintype "bidirectional"))
    )
    (net (code "53") (name "PA1") (class "Default")
      (node (ref "U1") (pin "11") (pinfunction "PA1_11") (pintype "bidirectional"))
    )
    (net (code "54") (name "PA2") (class "Default")
      (node (ref "R23") (pin "2") (pinfunction "2_2") (pintype "passive"))
      (node (ref "U1") (pin "12") (pinfunction "PA2_12") (pintype "bidirectional"))
    )
    (net (code "55") (name "PA3") (class "Default")
      (node (ref "U1") (pin "13") (pinfunction "PA3_13") (pintype "bidirectional"))
    )
    (net (code "56") (name "PA4") (class "Default")
      (node (ref "U1") (pin "14") (pinfunction "PA4_14") (pintype "bidirectional"))
    )
    (net (code "57") (name "PB5") (class "Default")
      (node (ref "Q13") (pin "3") (pinfunction "G_3") (pintype "passive"))
      (node (ref "U1") (pin "41") (pinfunction "PB5_41") (pintype "bidirectional"))
    )
    (net (code "58") (name "PB13") (class "Default")
      (node (ref "U1") (pin "26") (pinfunction "PB13_26") (pintype "bidirectional"))
    )
    (net (code "59") (name "PB14") (class "Default")
      (node (ref "C7") (pin "2") (pinfunction "2_2") (pintype "passive"))
      (node (ref "R2") (pin "1") (pinfunction "1_1") (pintype "passive"))
      (node (ref "U1") (pin "27") (pinfunction "PB14_27") (pintype "bidirectional"))
    )
    (net (code "60") (name "PB15") (class "Default")
      (node (ref "U1") (pin "28") (pinfunction "PB15_28") (pintype "bidirectional"))
    )
    (net (code "61") (name "RESET") (class "Default")
      (node (ref "Q7") (pin "1") (pinfunction "D_1") (pintype "passive"))
      (node (ref "U3") (pin "9") (pinfunction "RESET_9") (pintype "bidirectional"))
    )
    (net (code "62") (name "RF") (class "Default")
      (node (ref "U4") (pin "9") (pinfunction "ANT_9") (pintype "bidirectional"))
    )
    (net (code "63") (name "RF_IN") (class "Default")
      (node (ref "C9") (pin "1") (pinfunction "1_1") (pintype "passive"))
      (node (ref "R8") (pin "1") (pinfunction "1_1") (pintype "passive"))
      (node (ref "U3") (pin "11") (pinfunction "RF_IN_11") (pintype "bidirectional"))
    )
    (net (code "64") (name "RF_RESET") (class "Default")
      (node (ref "U1") (pin "18") (pinfunction "PB0_18") (pintype "bidirectional"))
      (node (ref "U4") (pin "6") (pinfunction "RESET_6") (pintype "bidirectional"))
    )
    (net (code "65") (name "RST") (class "Default")
      (node (ref "RST") (pin "P$1") (pinfunction "P$1_P$1") (pintype "bidirectional"))
      (node (ref "U1") (pin "7") (pinfunction "NRST_7") (pintype "bidirectional"))
    )
    (net (code "66") (name "RXD_MODULE") (class "Default")
      (node (ref "U1") (pin "42") (pinfunction "PB6_42") (pintype "bidirectional"))
      (node (ref "U3") (pin "3") (pinfunction "RXD_3") (pintype "bidirectional"))
    )
    (net (code "67") (name "SCK") (class "Default")
      (node (ref "U1") (pin "15") (pinfunction "PA5_15") (pintype "bidirectional"))
      (node (ref "U4") (pin "4") (pinfunction "SCK_4") (pintype "bidirectional"))
    )
    (net (code "68") (name "SCL") (class "Default")
      (node (ref "R14") (pin "1") (pinfunction "1_1") (pintype "passive"))
      (node (ref "U1") (pin "30") (pinfunction "PA9_30") (pintype "bidirectional"))
      (node (ref "U2") (pin "23") (pinfunction "SCL_23") (pintype "bidirectional"))
    )
    (net (code "69") (name "SDA") (class "Default")
      (node (ref "R7") (pin "1") (pinfunction "1_1") (pintype "passive"))
      (node (ref "U1") (pin "31") (pinfunction "PA10_31") (pintype "bidirectional"))
      (node (ref "U2") (pin "24") (pinfunction "SDA_24") (pintype "bidirectional"))
    )
    (net (code "70") (name "STANDBY") (class "Default")
      (node (ref "Q12") (pin "1") (pinfunction "D_1") (pintype "passive"))
      (node (ref "U3") (pin "5") (pinfunction "STANDBY_5") (pintype "bidirectional"))
    )
    (net (code "71") (name "SWCLK") (class "Default")
      (node (ref "D2") (pin "P$2") (pinfunction "2_P$2") (pintype "passive"))
      (node (ref "J2") (pin "P3") (pinfunction "D+_P3") (pintype "bidirectional"))
      (node (ref "R29") (pin "2") (pinfunction "2_2") (pintype "passive"))
      (node (ref "U1") (pin "37") (pinfunction "PA14_37") (pintype "bidirectional"))
    )
    (net (code "72") (name "SWDIO") (class "Default")
      (node (ref "D3") (pin "P$2") (pinfunction "2_P$2") (pintype "passive"))
      (node (ref "J2") (pin "P2") (pinfunction "D-_P2") (pintype "bidirectional"))
      (node (ref "R30") (pin "1") (pinfunction "1_1") (pintype "passive"))
      (node (ref "U1") (pin "34") (pinfunction "PA13_34") (pintype "bidirectional"))
    )
    (net (code "73") (name "TXD_MODULE") (class "Default")
      (node (ref "U1") (pin "43") (pinfunction "PB7_43") (pintype "bidirectional"))
      (node (ref "U3") (pin "2") (pinfunction "TXD_2") (pintype "bidirectional"))
    )
    (net (code "74") (name "UGND") (class "Default")
      (node (ref "J2") (pin "P5") (pinfunction "GND_P5") (pintype "passive"))
      (node (ref "L4") (pin "2") (pinfunction "P$2_2") (pintype "bidirectional"))
    )
    (net (code "75") (name "USBID") (class "Default")
      (node (ref "J2") (pin "P4") (pinfunction "ID_P4") (pintype "bidirectional"))
    )
    (net (code "76") (name "USB_5V") (class "Default")
      (node (ref "C16") (pin "1") (pinfunction "1_1") (pintype "passive"))
      (node (ref "C19") (pin "+") (pinfunction "+_+") (pintype "passive"))
      (node (ref "C20") (pin "1") (pinfunction "1_1") (pintype "passive"))
      (node (ref "CHRG") (pin "A") (pinfunction "A_A") (pintype "passive"))
      (node (ref "DD2") (pin "A") (pinfunction "A_A") (pintype "passive"))
      (node (ref "F1") (pin "1") (pinfunction "1_1") (pintype "passive"))
      (node (ref "FAULT") (pin "A") (pinfunction "A_A") (pintype "passive"))
      (node (ref "Q4") (pin "3") (pinfunction "G_3") (pintype "passive"))
      (node (ref "R12") (pin "2") (pinfunction "2_2") (pintype "passive"))
      (node (ref "R18") (pin "2") (pinfunction "2_2") (pintype "passive"))
      (node (ref "U5") (pin "4") (pinfunction "VIN_4") (pintype "bidirectional"))
      (node (ref "U5") (pin "8") (pinfunction "CE_8") (pintype "bidirectional"))
    )
    (net (code "77") (name "VCC_RF") (class "Default")
      (node (ref "U3") (pin "14") (pinfunction "VCC_RF_14") (pintype "bidirectional"))
    )
    (net (code "78") (name "XUSB") (class "Default")
      (node (ref "F1") (pin "2") (pinfunction "2_2") (pintype "passive"))
      (node (ref "J2") (pin "P1") (pinfunction "VBUS_P1") (pintype "power_in"))
    )
    (net (code "79") (name "unconnected-(K3-Pad2)") (class "Default")
      (node (ref "K3") (pin "2") (pinfunction "2_2") (pintype "passive"))
    )
    (net (code "80") (name "unconnected-(U2-AUX_CL-Pad7)") (class "Default")
      (node (ref "U2") (pin "7") (pinfunction "AUX_CL_7") (pintype "bidirectional"))
    )
    (net (code "81") (name "unconnected-(U2-AUX_DA-Pad21)") (class "Default")
      (node (ref "U2") (pin "21") (pinfunction "AUX_DA_21") (pintype "bidirectional"))
    )
    (net (code "82") (name "unconnected-(U2-NC-Pad2)") (class "Default")
      (node (ref "U2") (pin "2") (pinfunction "NC_2") (pintype "bidirectional"))
    )
    (net (code "83") (name "unconnected-(U2-NC-Pad3)") (class "Default")
      (node (ref "U2") (pin "3") (pinfunction "NC_3") (pintype "bidirectional"))
    )
    (net (code "84") (name "unconnected-(U2-NC-Pad4)") (class "Default")
      (node (ref "U2") (pin "4") (pinfunction "NC_4") (pintype "bidirectional"))
    )
    (net (code "85") (name "unconnected-(U2-NC-Pad5)") (class "Default")
      (node (ref "U2") (pin "5") (pinfunction "NC_5") (pintype "input"))
    )
    (net (code "86") (name "unconnected-(U2-NC-Pad6)") (class "Default")
      (node (ref "U2") (pin "6") (pinfunction "NC_6") (pintype "bidirectional"))
    )
    (net (code "87") (name "unconnected-(U2-NC-Pad14)") (class "Default")
      (node (ref "U2") (pin "14") (pinfunction "NC_14") (pintype "bidirectional"))
    )
    (net (code "88") (name "unconnected-(U2-NC-Pad15)") (class "Default")
      (node (ref "U2") (pin "15") (pinfunction "NC_15") (pintype "bidirectional"))
    )
    (net (code "89") (name "unconnected-(U2-NC-Pad16)") (class "Default")
      (node (ref "U2") (pin "16") (pinfunction "NC_16") (pintype "bidirectional"))
    )
    (net (code "90") (name "unconnected-(U2-NC-Pad17)") (class "Default")
      (node (ref "U2") (pin "17") (pinfunction "NC_17") (pintype "bidirectional"))
    )
    (net (code "91") (name "unconnected-(U2-RESV-Pad19)") (class "Default")
      (node (ref "U2") (pin "19") (pinfunction "RESV_19") (pintype "bidirectional"))
    )
    (net (code "92") (name "unconnected-(U3-NC-Pad7)") (class "Default")
      (node (ref "U3") (pin "7") (pinfunction "NC_7") (pintype "bidirectional"))
    )
    (net (code "93") (name "unconnected-(U3-NC-Pad15)") (class "Default")
      (node (ref "U3") (pin "15") (pinfunction "NC_15") (pintype "bidirectional"))
    )
  )
)
